# IR_1E1R.net
KiCad netlist of a schematic drawn in EAGLE
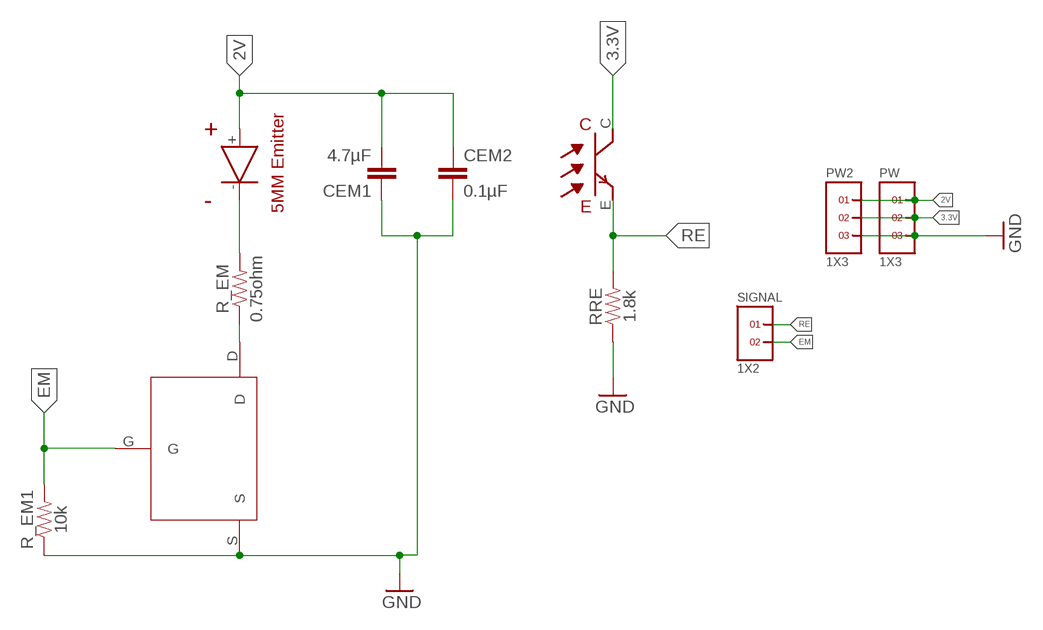
[diagram p0: schematic, sheet 1]

(export (version "E")
  (design (tool "Eeschema 10.0.6"))
  (components
    (comp (ref "CEM1")
      (value "4.7µF")
      (footprint "eagle-import:0805")
      (libsource (lib "eagle-import") (part "0.33UF/330NF-0805-50V-10%"))
    )
    (comp (ref "CEM2")
      (value "0.1µF")
      (footprint "eagle-import:0805")
      (libsource (lib "eagle-import") (part "0.33UF/330NF-0805-50V-10%"))
    )
    (comp (ref "PW")
      (value "1X3")
      (footprint "eagle-import:1X3")
      (libsource (lib "eagle-import") (part "1X3"))
    )
    (comp (ref "PW2")
      (value "1X3")
      (footprint "eagle-import:1X3")
      (libsource (lib "eagle-import") (part "1X3"))
    )
    (comp (ref "RECEIVER")
      (value "RECEIVER")
      (footprint "eagle-import:RECEIVER")
      (libsource (lib "eagle-import") (part "RECEIVER"))
    )
    (comp (ref "RRE")
      (value "1.8k")
      (footprint "eagle-import:0805")
      (libsource (lib "eagle-import") (part "0.75OHM-0805-1/4W-1%"))
    )
    (comp (ref "R_EM")
      (value "0.75ohm")
      (footprint "eagle-import:0805")
      (libsource (lib "eagle-import") (part "0.75OHM-0805-1/4W-1%"))
    )
    (comp (ref "R_EM1")
      (value "10k")
      (footprint "eagle-import:0805")
      (libsource (lib "eagle-import") (part "0.75OHM-0805-1/4W-1%"))
    )
    (comp (ref "SIGNAL")
      (value "1X2")
      (footprint "eagle-import:1X2")
      (libsource (lib "eagle-import") (part "1X2"))
    )
    (comp (ref "U$1")
      (value "MCH3474")
      (footprint "eagle-import:MCH3474")
      (libsource (lib "eagle-import") (part "MCH3474"))
    )
    (comp (ref "U$21")
      (value "EMITTER")
      (footprint "eagle-import:EMITTER")
      (libsource (lib "eagle-import") (part "EMITTER"))
    )
  )
  (nets
    (net (code "1") (name "2V") (class "Default")
      (node (ref "CEM1") (pin "2") (pinfunction "2_2") (pintype "passive"))
      (node (ref "CEM2") (pin "1") (pinfunction "1_1") (pintype "passive"))
      (node (ref "PW") (pin "1") (pinfunction "1_1") (pintype "bidirectional"))
      (node (ref "PW2") (pin "1") (pinfunction "1_1") (pintype "bidirectional"))
      (node (ref "U$21") (pin "+") (pinfunction "+_+") (pintype "bidirectional"))
    )
    (net (code "2") (name "3.3V") (class "Default")
      (node (ref "PW") (pin "2") (pinfunction "2_2") (pintype "bidirectional"))
      (node (ref "PW2") (pin "2") (pinfunction "2_2") (pintype "bidirectional"))
      (node (ref "RECEIVER") (pin "C") (pinfunction "C_C") (pintype "bidirectional"))
    )
    (net (code "3") (name "EM") (class "Default")
      (node (ref "R_EM1") (pin "2") (pinfunction "2_2") (pintype "passive"))
      (node (ref "SIGNAL") (pin "2") (pinfunction "2_2") (pintype "bidirectional"))
      (node (ref "U$1") (pin "G") (pinfunction "G_G") (pintype "bidirectional"))
    )
    (net (code "4") (name "GND") (class "Default")
      (node (ref "CEM1") (pin "1") (pinfunction "1_1") (pintype "passive"))
      (node (ref "CEM2") (pin "2") (pinfunction "2_2") (pintype "passive"))
      (node (ref "PW") (pin "3") (pinfunction "3_3") (pintype "bidirectional"))
      (node (ref "PW2") (pin "3") (pinfunction "3_3") (pintype "bidirectional"))
      (node (ref "RRE") (pin "1") (pinfunction "1_1") (pintype "passive"))
      (node (ref "R_EM1") (pin "1") (pinfunction "1_1") (pintype "passive"))
      (node (ref "U$1") (pin "S") (pinfunction "S_S") (pintype "bidirectional"))
    )
    (net (code "5") (name "Net-(R_EM-Pad1)") (class "Default")
      (node (ref "R_EM") (pin "1") (pinfunction "1_1") (pintype "passive"))
      (node (ref "U$1") (pin "D") (pinfunction "D_D") (pintype "bidirectional"))
    )
    (net (code "6") (name "Net-(R_EM-Pad2)") (class "Default")
      (node (ref "R_EM") (pin "2") (pinfunction "2_2") (pintype "passive"))
      (node (ref "U$21") (pin "-") (pinfunction "-_-") (pintype "bidirectional"))
    )
    (net (code "7") (name "RE") (class "Default")
      (node (ref "RECEIVER") (pin "E") (pinfunction "E_E") (pintype "bidirectional"))
      (node (ref "RRE") (pin "2") (pinfunction "2_2") (pintype "passive"))
      (node (ref "SIGNAL") (pin "1") (pinfunction "1_1") (pintype "bidirectional"))
    )
  )
)
